# TIEVOX_Power.net
KiCad netlist of a schematic drawn in EAGLE
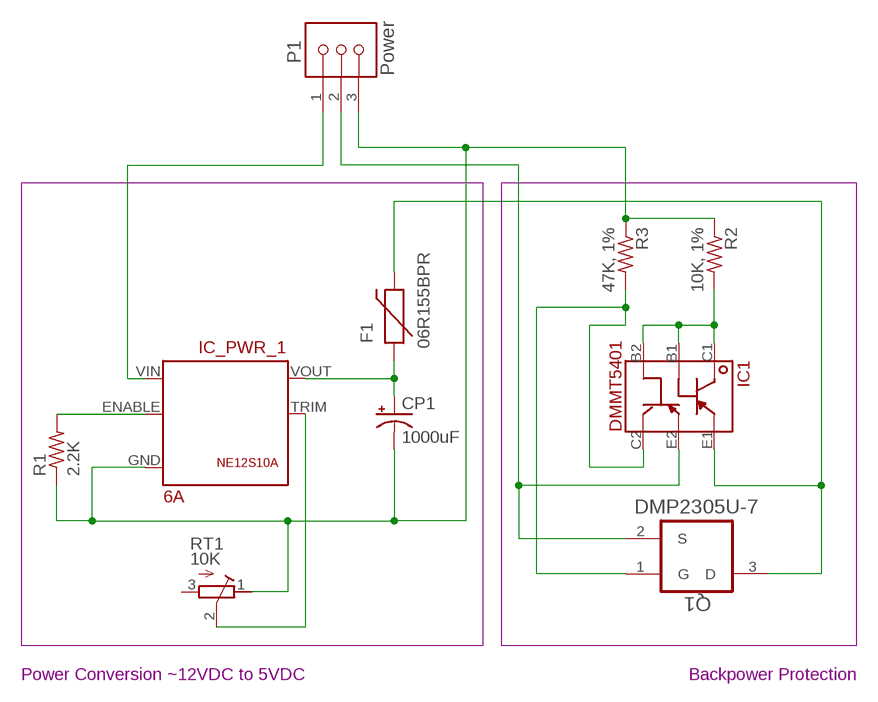
[diagram p0: schematic, sheet 1]

(export (version "E")
  (design (tool "Eeschema 10.0.6"))
  (components
    (comp (ref "CP1")
      (value "1000uF")
      (footprint "eagle-import:E3,5-8")
      (libsource (lib "eagle-import") (part "CPOL-USE3.5-8"))
    )
    (comp (ref "F1")
      (value "06R155BPR")
      (footprint "eagle-import:PTC")
      (libsource (lib "eagle-import") (part "PTCPTH"))
    )
    (comp (ref "IC1")
      (value "DMMT5401")
      (footprint "eagle-import:DMMT5401")
      (libsource (lib "eagle-import") (part "DMMT5401DMMT"))
    )
    (comp (ref "IC_PWR_1")
      (value "6A")
      (footprint "eagle-import:NE12S")
      (libsource (lib "eagle-import") (part "NE12S12V6A"))
    )
    (comp (ref "P1")
      (value "Power")
      (footprint "eagle-import:PINHEAD-LOCK-3")
      (fields (field (name "PARTNUM") "22-23-2031"))
      (libsource (lib "eagle-import") (part "CONN3-L"))
    )
    (comp (ref "Q1")
      (value "DMP2305U-7")
      (footprint "eagle-import:SOT103P240X110-3N")
      (libsource (lib "eagle-import") (part "DMP2305U-7"))
    )
    (comp (ref "R1")
      (value "2.2K")
      (footprint "eagle-import:0207_10")
      (libsource (lib "eagle-import") (part "R-US_0207/10"))
    )
    (comp (ref "R2")
      (value "10K, 1%")
      (footprint "eagle-import:0207_7")
      (libsource (lib "eagle-import") (part "R-US_0207/7"))
    )
    (comp (ref "R3")
      (value "47K, 1%")
      (footprint "eagle-import:0207_7")
      (libsource (lib "eagle-import") (part "R-US_0207/7"))
    )
    (comp (ref "RT1")
      (value "10K")
      (footprint "eagle-import:RTRIM3006P")
      (libsource (lib "eagle-import") (part "R-TRIMM3006P"))
    )
  )
  (nets
    (net (code "1") (name "Net-(F1-1)") (class "Default")
      (node (ref "CP1") (pin "+") (pinfunction "+_+") (pintype "passive"))
      (node (ref "F1") (pin "P$1") (pinfunction "1_P$1") (pintype "bidirectional"))
      (node (ref "IC_PWR_1") (pin "VOUT") (pinfunction "VOUT_VOUT") (pintype "power_in"))
    )
    (net (code "2") (name "Net-(F1-2)") (class "Default")
      (node (ref "F1") (pin "P$2") (pinfunction "2_P$2") (pintype "bidirectional"))
      (node (ref "IC1") (pin "E1") (pinfunction "E1_E1") (pintype "bidirectional"))
      (node (ref "Q1") (pin "3") (pinfunction "D_3") (pintype "output"))
    )
    (net (code "3") (name "Net-(IC1-PadB1)") (class "Default")
      (node (ref "IC1") (pin "B1") (pinfunction "B1_B1") (pintype "bidirectional"))
      (node (ref "IC1") (pin "B2") (pinfunction "B2_B2") (pintype "bidirectional"))
      (node (ref "IC1") (pin "C1") (pinfunction "C1_C1") (pintype "bidirectional"))
      (node (ref "R2") (pin "2") (pinfunction "2_2") (pintype "passive"))
    )
    (net (code "4") (name "Net-(IC_PWR_1-PadENABLE)") (class "Default")
      (node (ref "IC_PWR_1") (pin "ENABLE") (pinfunction "ENABLE_ENABLE") (pintype "input"))
      (node (ref "R1") (pin "2") (pinfunction "2_2") (pintype "passive"))
    )
    (net (code "5") (name "Net-(IC_PWR_1-PadVIN)") (class "Default")
      (node (ref "IC_PWR_1") (pin "VIN") (pinfunction "VIN_VIN") (pintype "power_in"))
      (node (ref "P1") (pin "1") (pinfunction "1_1") (pintype "bidirectional"))
    )
    (net (code "6") (name "Net-(Q1-G)") (class "Default")
      (node (ref "IC1") (pin "C2") (pinfunction "C2_C2") (pintype "bidirectional"))
      (node (ref "Q1") (pin "1") (pinfunction "G_1") (pintype "input"))
      (node (ref "R3") (pin "2") (pinfunction "2_2") (pintype "passive"))
    )
    (net (code "7") (name "Net-(Q1-S)") (class "Default")
      (node (ref "IC1") (pin "E2") (pinfunction "E2_E2") (pintype "bidirectional"))
      (node (ref "P1") (pin "2") (pinfunction "2_2") (pintype "bidirectional"))
      (node (ref "Q1") (pin "2") (pinfunction "S_2") (pintype "passive"))
    )
    (net (code "8") (name "Net-(RT1-E)") (class "Default")
      (node (ref "CP1") (pin "-") (pinfunction "-_-") (pintype "passive"))
      (node (ref "IC_PWR_1") (pin "GND") (pinfunction "GND_GND") (pintype "power_in"))
      (node (ref "P1") (pin "3") (pinfunction "3_3") (pintype "bidirectional"))
      (node (ref "R1") (pin "1") (pinfunction "1_1") (pintype "passive"))
      (node (ref "R2") (pin "1") (pinfunction "1_1") (pintype "passive"))
      (node (ref "R3") (pin "1") (pinfunction "1_1") (pintype "passive"))
      (node (ref "RT1") (pin "1") (pinfunction "E_1") (pintype "passive"))
    )
    (net (code "9") (name "Net-(RT1-S)") (class "Default")
      (node (ref "IC_PWR_1") (pin "TRIM") (pinfunction "TRIM_TRIM") (pintype "power_in"))
      (node (ref "RT1") (pin "2") (pinfunction "S_2") (pintype "passive"))
    )
    (net (code "10") (name "unconnected-(RT1-A-Pad3)") (class "Default")
      (node (ref "RT1") (pin "3") (pinfunction "A_3") (pintype "passive"))
    )
  )
)
